# Wheatstone_bridge_part_I.net
KiCad netlist of a schematic drawn in Altium Designer
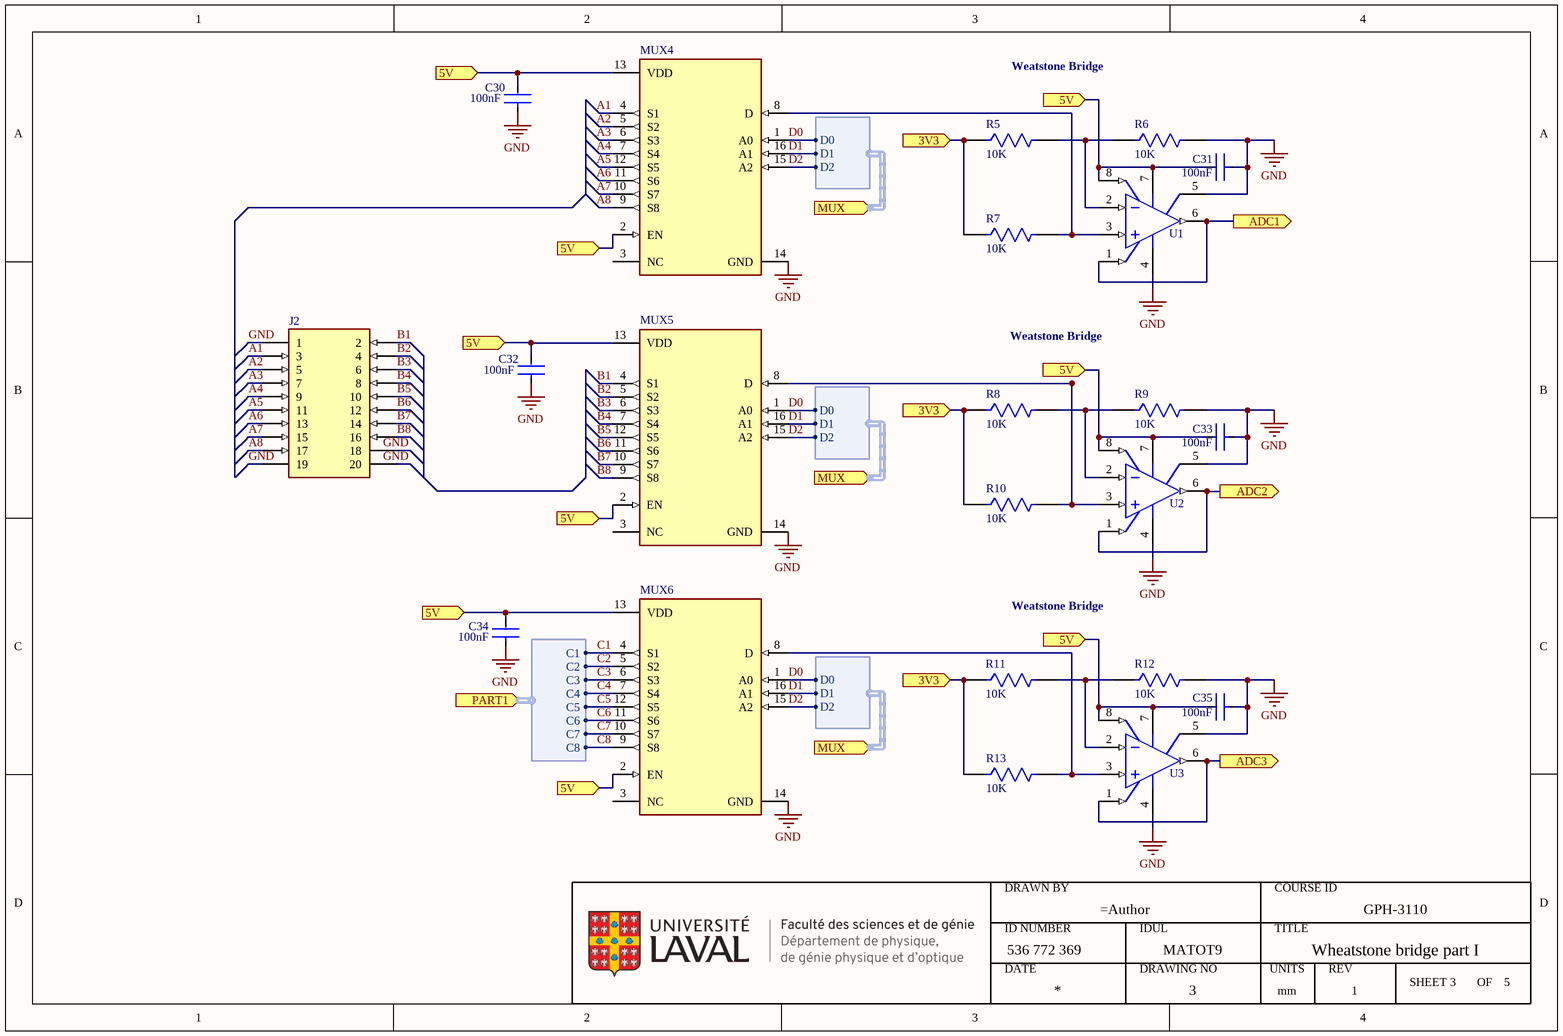
[diagram p0: Wheatstone bridge part I.SchDoc]

(export (version "E")
  (design (tool "Eeschema 10.0.6"))
  (components
    (comp (ref "*3")
      (value "ULaval FSG-DPGPO")
      (libsource (lib "ULaval Title Block") (part "ULaval FSG-DPGPO"))
    )
    (comp (ref "C30")
      (value "100nF")
      (footprint "FP-CC0603-DA-IPC_B")
      (description "0603 0.1 uF 50 V ±5 % Tolerance X7R SMT Multilayer Ceramic Capacitor")
      (fields (field (name "TOLERANCE") "5%") (field (name "Comment") "CC0603JRX7R9BB104"))
      (libsource (lib "Laval University") (part "02cd4be3c70576c341d710602a673aa"))
    )
    (comp (ref "C31")
      (value "100nF")
      (footprint "FP-CC0603-DA-IPC_B")
      (description "0603 0.1 uF 50 V ±5 % Tolerance X7R SMT Multilayer Ceramic Capacitor")
      (fields (field (name "TOLERANCE") "5%") (field (name "Comment") "CC0603JRX7R9BB104"))
      (libsource (lib "Laval University") (part "02cd4be3c70576c341d710602a673aa"))
    )
    (comp (ref "C32")
      (value "100nF")
      (footprint "FP-CC0603-DA-IPC_B")
      (description "0603 0.1 uF 50 V ±5 % Tolerance X7R SMT Multilayer Ceramic Capacitor")
      (fields (field (name "TOLERANCE") "5%") (field (name "Comment") "CC0603JRX7R9BB104"))
      (libsource (lib "Laval University") (part "02cd4be3c70576c341d710602a673aa"))
    )
    (comp (ref "C33")
      (value "100nF")
      (footprint "FP-CC0603-DA-IPC_B")
      (description "0603 0.1 uF 50 V ±5 % Tolerance X7R SMT Multilayer Ceramic Capacitor")
      (fields (field (name "TOLERANCE") "5%") (field (name "Comment") "CC0603JRX7R9BB104"))
      (libsource (lib "Laval University") (part "02cd4be3c70576c341d710602a673aa"))
    )
    (comp (ref "C34")
      (value "100nF")
      (footprint "FP-CC0603-DA-IPC_B")
      (description "0603 0.1 uF 50 V ±5 % Tolerance X7R SMT Multilayer Ceramic Capacitor")
      (fields (field (name "TOLERANCE") "5%") (field (name "Comment") "CC0603JRX7R9BB104"))
      (libsource (lib "Laval University") (part "02cd4be3c70576c341d710602a673aa"))
    )
    (comp (ref "C35")
      (value "100nF")
      (footprint "FP-CC0603-DA-IPC_B")
      (description "0603 0.1 uF 50 V ±5 % Tolerance X7R SMT Multilayer Ceramic Capacitor")
      (fields (field (name "TOLERANCE") "5%") (field (name "Comment") "CC0603JRX7R9BB104"))
      (libsource (lib "Laval University") (part "02cd4be3c70576c341d710602a673aa"))
    )
    (comp (ref "J2")
      (value "SFC-110-T1-F-D-A")
      (footprint "SFC-110-T1-F-D-A-Footprint-2")
      (description "Headers & Wire Housings .050 Tiger Eye Cost-Effective Reliable Socket Strip")
      (libsource (lib "Laval University") (part "SFC-110-T1-F-D-A"))
    )
    (comp (ref "MUX4")
      (value "TMUX1208PWR")
      (footprint "TMUX1208PWR")
      (description "5-V, 8: 1, 1-channel general-purpose analog multiplexer with 1.8-V input logic 16-TSSOP -40 to 125")
      (libsource (lib "Arduino Nano Every Symbols") (part "TMUX1208PWR"))
    )
    (comp (ref "MUX5")
      (value "TMUX1208PWR")
      (footprint "TMUX1208PWR")
      (description "5-V, 8: 1, 1-channel general-purpose analog multiplexer with 1.8-V input logic 16-TSSOP -40 to 125")
      (libsource (lib "Arduino Nano Every Symbols") (part "TMUX1208PWR"))
    )
    (comp (ref "MUX6")
      (value "TMUX1208PWR")
      (footprint "TMUX1208PWR")
      (description "5-V, 8: 1, 1-channel general-purpose analog multiplexer with 1.8-V input logic 16-TSSOP -40 to 125")
      (libsource (lib "Arduino Nano Every Symbols") (part "TMUX1208PWR"))
    )
    (comp (ref "R5")
      (value "10K")
      (footprint "FP-RT0603-IPC_B")
      (description "Res High precision Thin Film 0603 10K Ohm 0.1% 1/10W ±25ppm/°C Molded SMD Paper T/R")
      (fields (field (name "Comment") "RT0603BRD0710KL"))
      (libsource (lib "Laval University") (part "1029c3af85768c4190bb7ad29bc67b5"))
    )
    (comp (ref "R6")
      (value "10K")
      (footprint "FP-RT0603-IPC_B")
      (description "Res High precision Thin Film 0603 10K Ohm 0.1% 1/10W ±25ppm/°C Molded SMD Paper T/R")
      (fields (field (name "Comment") "RT0603BRD0710KL"))
      (libsource (lib "Laval University") (part "1029c3af85768c4190bb7ad29bc67b5"))
    )
    (comp (ref "R7")
      (value "10K")
      (footprint "FP-RT0603-IPC_B")
      (description "Res High precision Thin Film 0603 10K Ohm 0.1% 1/10W ±25ppm/°C Molded SMD Paper T/R")
      (fields (field (name "Comment") "RT0603BRD0710KL"))
      (libsource (lib "Laval University") (part "1029c3af85768c4190bb7ad29bc67b5"))
    )
    (comp (ref "R8")
      (value "10K")
      (footprint "FP-RT0603-IPC_B")
      (description "Res High precision Thin Film 0603 10K Ohm 0.1% 1/10W ±25ppm/°C Molded SMD Paper T/R")
      (fields (field (name "Comment") "RT0603BRD0710KL"))
      (libsource (lib "Laval University") (part "1029c3af85768c4190bb7ad29bc67b5"))
    )
    (comp (ref "R9")
      (value "10K")
      (footprint "FP-RT0603-IPC_B")
      (description "Res High precision Thin Film 0603 10K Ohm 0.1% 1/10W ±25ppm/°C Molded SMD Paper T/R")
      (fields (field (name "Comment") "RT0603BRD0710KL"))
      (libsource (lib "Laval University") (part "1029c3af85768c4190bb7ad29bc67b5"))
    )
    (comp (ref "R10")
      (value "10K")
      (footprint "FP-RT0603-IPC_B")
      (description "Res High precision Thin Film 0603 10K Ohm 0.1% 1/10W ±25ppm/°C Molded SMD Paper T/R")
      (fields (field (name "Comment") "RT0603BRD0710KL"))
      (libsource (lib "Laval University") (part "1029c3af85768c4190bb7ad29bc67b5"))
    )
    (comp (ref "R11")
      (value "10K")
      (footprint "FP-RT0603-IPC_B")
      (description "Res High precision Thin Film 0603 10K Ohm 0.1% 1/10W ±25ppm/°C Molded SMD Paper T/R")
      (fields (field (name "Comment") "RT0603BRD0710KL"))
      (libsource (lib "Laval University") (part "1029c3af85768c4190bb7ad29bc67b5"))
    )
    (comp (ref "R12")
      (value "10K")
      (footprint "FP-RT0603-IPC_B")
      (description "Res High precision Thin Film 0603 10K Ohm 0.1% 1/10W ±25ppm/°C Molded SMD Paper T/R")
      (fields (field (name "Comment") "RT0603BRD0710KL"))
      (libsource (lib "Laval University") (part "1029c3af85768c4190bb7ad29bc67b5"))
    )
    (comp (ref "R13")
      (value "10K")
      (footprint "FP-RT0603-IPC_B")
      (description "Res High precision Thin Film 0603 10K Ohm 0.1% 1/10W ±25ppm/°C Molded SMD Paper T/R")
      (fields (field (name "Comment") "RT0603BRD0710KL"))
      (libsource (lib "Laval University") (part "1029c3af85768c4190bb7ad29bc67b5"))
    )
    (comp (ref "U1")
      (value "MCP6N11-100E/SN")
      (footprint "MCP6N11-100E/SN")
      (description "MCP6N11 Series Single Channel 500 KHz 5.5 V Instrumentation Amplifier - SOIC-8")
      (libsource (lib "Laval University") (part "AMP-INA-MCP6N11-IL8"))
    )
    (comp (ref "U2")
      (value "MCP6N11-100E/SN")
      (footprint "MCP6N11-100E/SN")
      (description "MCP6N11 Series Single Channel 500 KHz 5.5 V Instrumentation Amplifier - SOIC-8")
      (libsource (lib "Laval University") (part "AMP-INA-MCP6N11-IL8"))
    )
    (comp (ref "U3")
      (value "MCP6N11-100E/SN")
      (footprint "MCP6N11-100E/SN")
      (description "MCP6N11 Series Single Channel 500 KHz 5.5 V Instrumentation Amplifier - SOIC-8")
      (libsource (lib "Laval University") (part "AMP-INA-MCP6N11-IL8"))
    )
  )
  (nets
    (net (code "3") (name "/3V3") (class "Default")
      (node (ref "R10") (pin "1") (pinfunction "1_1") (pintype "passive"))
      (node (ref "R11") (pin "1") (pinfunction "1_1") (pintype "passive"))
      (node (ref "R13") (pin "1") (pinfunction "1_1") (pintype "passive"))
      (node (ref "R5") (pin "1") (pinfunction "1_1") (pintype "passive"))
      (node (ref "R7") (pin "1") (pinfunction "1_1") (pintype "passive"))
      (node (ref "R8") (pin "1") (pinfunction "1_1") (pintype "passive"))
    )
    (net (code "4") (name "/5V") (class "Default")
      (node (ref "C30") (pin "2") (pinfunction "2_2") (pintype "passive"))
      (node (ref "C31") (pin "2") (pinfunction "2_2") (pintype "passive"))
      (node (ref "C32") (pin "2") (pinfunction "2_2") (pintype "passive"))
      (node (ref "C33") (pin "2") (pinfunction "2_2") (pintype "passive"))
      (node (ref "C34") (pin "2") (pinfunction "2_2") (pintype "passive"))
      (node (ref "C35") (pin "2") (pinfunction "2_2") (pintype "passive"))
      (node (ref "MUX4") (pin "13") (pinfunction "VDD_13") (pintype "power_in"))
      (node (ref "MUX4") (pin "2") (pinfunction "EN_2") (pintype "input"))
      (node (ref "MUX5") (pin "13") (pinfunction "VDD_13") (pintype "power_in"))
      (node (ref "MUX5") (pin "2") (pinfunction "EN_2") (pintype "input"))
      (node (ref "MUX6") (pin "13") (pinfunction "VDD_13") (pintype "power_in"))
      (node (ref "MUX6") (pin "2") (pinfunction "EN_2") (pintype "input"))
      (node (ref "U1") (pin "7") (pinfunction "VDD_7") (pintype "power_in"))
      (node (ref "U1") (pin "8") (pinfunction "EN/~{CAL}_8") (pintype "input"))
      (node (ref "U2") (pin "7") (pinfunction "VDD_7") (pintype "power_in"))
      (node (ref "U2") (pin "8") (pinfunction "EN/~{CAL}_8") (pintype "input"))
      (node (ref "U3") (pin "7") (pinfunction "VDD_7") (pintype "power_in"))
      (node (ref "U3") (pin "8") (pinfunction "EN/~{CAL}_8") (pintype "input"))
    )
    (net (code "5") (name "/A1") (class "Default")
      (node (ref "J2") (pin "3") (pinfunction "3_3") (pintype "input"))
      (node (ref "MUX4") (pin "4") (pinfunction "S1_4") (pintype "output"))
    )
    (net (code "6") (name "/A2") (class "Default")
      (node (ref "J2") (pin "5") (pinfunction "5_5") (pintype "input"))
      (node (ref "MUX4") (pin "5") (pinfunction "S2_5") (pintype "output"))
    )
    (net (code "7") (name "/A3") (class "Default")
      (node (ref "J2") (pin "7") (pinfunction "7_7") (pintype "input"))
      (node (ref "MUX4") (pin "6") (pinfunction "S3_6") (pintype "output"))
    )
    (net (code "8") (name "/A4") (class "Default")
      (node (ref "J2") (pin "9") (pinfunction "9_9") (pintype "input"))
      (node (ref "MUX4") (pin "7") (pinfunction "S4_7") (pintype "output"))
    )
    (net (code "9") (name "/A5") (class "Default")
      (node (ref "J2") (pin "11") (pinfunction "11_11") (pintype "input"))
      (node (ref "MUX4") (pin "12") (pinfunction "S5_12") (pintype "output"))
    )
    (net (code "10") (name "/A6") (class "Default")
      (node (ref "J2") (pin "13") (pinfunction "13_13") (pintype "input"))
      (node (ref "MUX4") (pin "11") (pinfunction "S6_11") (pintype "output"))
    )
    (net (code "11") (name "/A7") (class "Default")
      (node (ref "J2") (pin "15") (pinfunction "15_15") (pintype "input"))
      (node (ref "MUX4") (pin "10") (pinfunction "S7_10") (pintype "output"))
    )
    (net (code "12") (name "/A8") (class "Default")
      (node (ref "J2") (pin "17") (pinfunction "17_17") (pintype "input"))
      (node (ref "MUX4") (pin "9") (pinfunction "S8_9") (pintype "output"))
    )
    (net (code "13") (name "/ADC1") (class "Default")
      (node (ref "U1") (pin "1") (pinfunction "VFG_1") (pintype "input"))
      (node (ref "U1") (pin "6") (pinfunction "VOUT_6") (pintype "output"))
    )
    (net (code "14") (name "/ADC2") (class "Default")
      (node (ref "U2") (pin "1") (pinfunction "VFG_1") (pintype "input"))
      (node (ref "U2") (pin "6") (pinfunction "VOUT_6") (pintype "output"))
    )
    (net (code "15") (name "/ADC3") (class "Default")
      (node (ref "U3") (pin "1") (pinfunction "VFG_1") (pintype "input"))
      (node (ref "U3") (pin "6") (pinfunction "VOUT_6") (pintype "output"))
    )
    (net (code "16") (name "/B1") (class "Default")
      (node (ref "J2") (pin "2") (pinfunction "2_2") (pintype "input"))
      (node (ref "MUX5") (pin "4") (pinfunction "S1_4") (pintype "output"))
    )
    (net (code "17") (name "/B2") (class "Default")
      (node (ref "J2") (pin "4") (pinfunction "4_4") (pintype "input"))
      (node (ref "MUX5") (pin "5") (pinfunction "S2_5") (pintype "output"))
    )
    (net (code "18") (name "/B3") (class "Default")
      (node (ref "J2") (pin "6") (pinfunction "6_6") (pintype "input"))
      (node (ref "MUX5") (pin "6") (pinfunction "S3_6") (pintype "output"))
    )
    (net (code "19") (name "/B4") (class "Default")
      (node (ref "J2") (pin "8") (pinfunction "8_8") (pintype "input"))
      (node (ref "MUX5") (pin "7") (pinfunction "S4_7") (pintype "output"))
    )
    (net (code "20") (name "/B5") (class "Default")
      (node (ref "J2") (pin "10") (pinfunction "10_10") (pintype "input"))
      (node (ref "MUX5") (pin "12") (pinfunction "S5_12") (pintype "output"))
    )
    (net (code "21") (name "/B6") (class "Default")
      (node (ref "J2") (pin "12") (pinfunction "12_12") (pintype "input"))
      (node (ref "MUX5") (pin "11") (pinfunction "S6_11") (pintype "output"))
    )
    (net (code "22") (name "/B7") (class "Default")
      (node (ref "J2") (pin "14") (pinfunction "14_14") (pintype "input"))
      (node (ref "MUX5") (pin "10") (pinfunction "S7_10") (pintype "output"))
    )
    (net (code "23") (name "/B8") (class "Default")
      (node (ref "J2") (pin "16") (pinfunction "16_16") (pintype "input"))
      (node (ref "MUX5") (pin "9") (pinfunction "S8_9") (pintype "output"))
    )
    (net (code "24") (name "/C1") (class "Default")
      (node (ref "MUX6") (pin "4") (pinfunction "S1_4") (pintype "output"))
    )
    (net (code "25") (name "/C2") (class "Default")
      (node (ref "MUX6") (pin "5") (pinfunction "S2_5") (pintype "output"))
    )
    (net (code "26") (name "/C3") (class "Default")
      (node (ref "MUX6") (pin "6") (pinfunction "S3_6") (pintype "output"))
    )
    (net (code "27") (name "/C4") (class "Default")
      (node (ref "MUX6") (pin "7") (pinfunction "S4_7") (pintype "output"))
    )
    (net (code "28") (name "/C5") (class "Default")
      (node (ref "MUX6") (pin "12") (pinfunction "S5_12") (pintype "output"))
    )
    (net (code "29") (name "/C6") (class "Default")
      (node (ref "MUX6") (pin "11") (pinfunction "S6_11") (pintype "output"))
    )
    (net (code "30") (name "/C7") (class "Default")
      (node (ref "MUX6") (pin "10") (pinfunction "S7_10") (pintype "output"))
    )
    (net (code "31") (name "/C8") (class "Default")
      (node (ref "MUX6") (pin "9") (pinfunction "S8_9") (pintype "output"))
    )
    (net (code "32") (name "/D0") (class "Default")
      (node (ref "MUX4") (pin "1") (pinfunction "A0_1") (pintype "input"))
      (node (ref "MUX5") (pin "1") (pinfunction "A0_1") (pintype "input"))
      (node (ref "MUX6") (pin "1") (pinfunction "A0_1") (pintype "input"))
    )
    (net (code "33") (name "/D1") (class "Default")
      (node (ref "MUX4") (pin "16") (pinfunction "A1_16") (pintype "input"))
      (node (ref "MUX5") (pin "16") (pinfunction "A1_16") (pintype "input"))
      (node (ref "MUX6") (pin "16") (pinfunction "A1_16") (pintype "input"))
    )
    (net (code "34") (name "/D2") (class "Default")
      (node (ref "MUX4") (pin "15") (pinfunction "A2_15") (pintype "input"))
      (node (ref "MUX5") (pin "15") (pinfunction "A2_15") (pintype "input"))
      (node (ref "MUX6") (pin "15") (pinfunction "A2_15") (pintype "input"))
    )
    (net (code "37") (name "GND") (class "Default")
      (node (ref "C30") (pin "1") (pinfunction "1_1") (pintype "passive"))
      (node (ref "C31") (pin "1") (pinfunction "1_1") (pintype "passive"))
      (node (ref "C32") (pin "1") (pinfunction "1_1") (pintype "passive"))
      (node (ref "C33") (pin "1") (pinfunction "1_1") (pintype "passive"))
      (node (ref "C34") (pin "1") (pinfunction "1_1") (pintype "passive"))
      (node (ref "C35") (pin "1") (pinfunction "1_1") (pintype "passive"))
      (node (ref "J2") (pin "1") (pinfunction "1_1") (pintype "power_in"))
      (node (ref "J2") (pin "18") (pinfunction "18_18") (pintype "power_in"))
      (node (ref "J2") (pin "19") (pinfunction "19_19") (pintype "power_in"))
      (node (ref "J2") (pin "20") (pinfunction "20_20") (pintype "power_in"))
      (node (ref "MUX4") (pin "14") (pinfunction "GND_14") (pintype "power_in"))
      (node (ref "MUX5") (pin "14") (pinfunction "GND_14") (pintype "power_in"))
      (node (ref "MUX6") (pin "14") (pinfunction "GND_14") (pintype "power_in"))
      (node (ref "R12") (pin "2") (pinfunction "2_2") (pintype "passive"))
      (node (ref "R6") (pin "2") (pinfunction "2_2") (pintype "passive"))
      (node (ref "R9") (pin "2") (pinfunction "2_2") (pintype "passive"))
      (node (ref "U1") (pin "4") (pinfunction "VSS_4") (pintype "power_in"))
      (node (ref "U1") (pin "5") (pinfunction "VREF_5") (pintype "power_in"))
      (node (ref "U2") (pin "4") (pinfunction "VSS_4") (pintype "power_in"))
      (node (ref "U2") (pin "5") (pinfunction "VREF_5") (pintype "power_in"))
      (node (ref "U3") (pin "4") (pinfunction "VSS_4") (pintype "power_in"))
      (node (ref "U3") (pin "5") (pinfunction "VREF_5") (pintype "power_in"))
    )
    (net (code "38") (name "Net-(MUX4-D)") (class "Default")
      (node (ref "MUX4") (pin "8") (pinfunction "D_8") (pintype "input"))
      (node (ref "R7") (pin "2") (pinfunction "2_2") (pintype "passive"))
      (node (ref "U1") (pin "3") (pinfunction "VIP_3") (pintype "input"))
    )
    (net (code "39") (name "Net-(MUX5-D)") (class "Default")
      (node (ref "MUX5") (pin "8") (pinfunction "D_8") (pintype "input"))
      (node (ref "R10") (pin "2") (pinfunction "2_2") (pintype "passive"))
      (node (ref "U2") (pin "3") (pinfunction "VIP_3") (pintype "input"))
    )
    (net (code "40") (name "Net-(MUX6-D)") (class "Default")
      (node (ref "MUX6") (pin "8") (pinfunction "D_8") (pintype "input"))
      (node (ref "R13") (pin "2") (pinfunction "2_2") (pintype "passive"))
      (node (ref "U3") (pin "3") (pinfunction "VIP_3") (pintype "input"))
    )
    (net (code "41") (name "Net-(U1-VIM)") (class "Default")
      (node (ref "R5") (pin "2") (pinfunction "2_2") (pintype "passive"))
      (node (ref "R6") (pin "1") (pinfunction "1_1") (pintype "passive"))
      (node (ref "U1") (pin "2") (pinfunction "VIM_2") (pintype "input"))
    )
    (net (code "42") (name "Net-(U2-VIM)") (class "Default")
      (node (ref "R8") (pin "2") (pinfunction "2_2") (pintype "passive"))
      (node (ref "R9") (pin "1") (pinfunction "1_1") (pintype "passive"))
      (node (ref "U2") (pin "2") (pinfunction "VIM_2") (pintype "input"))
    )
    (net (code "43") (name "Net-(U3-VIM)") (class "Default")
      (node (ref "R11") (pin "2") (pinfunction "2_2") (pintype "passive"))
      (node (ref "R12") (pin "1") (pinfunction "1_1") (pintype "passive"))
      (node (ref "U3") (pin "2") (pinfunction "VIM_2") (pintype "input"))
    )
    (net (code "44") (name "unconnected-(MUX4-NC-Pad3)") (class "Default")
      (node (ref "MUX4") (pin "3") (pinfunction "NC_3") (pintype "tri_state"))
    )
    (net (code "45") (name "unconnected-(MUX5-NC-Pad3)") (class "Default")
      (node (ref "MUX5") (pin "3") (pinfunction "NC_3") (pintype "tri_state"))
    )
    (net (code "46") (name "unconnected-(MUX6-NC-Pad3)") (class "Default")
      (node (ref "MUX6") (pin "3") (pinfunction "NC_3") (pintype "tri_state"))
    )
  )
)
